# usb-serial.net
KiCad netlist of a schematic drawn in EAGLE
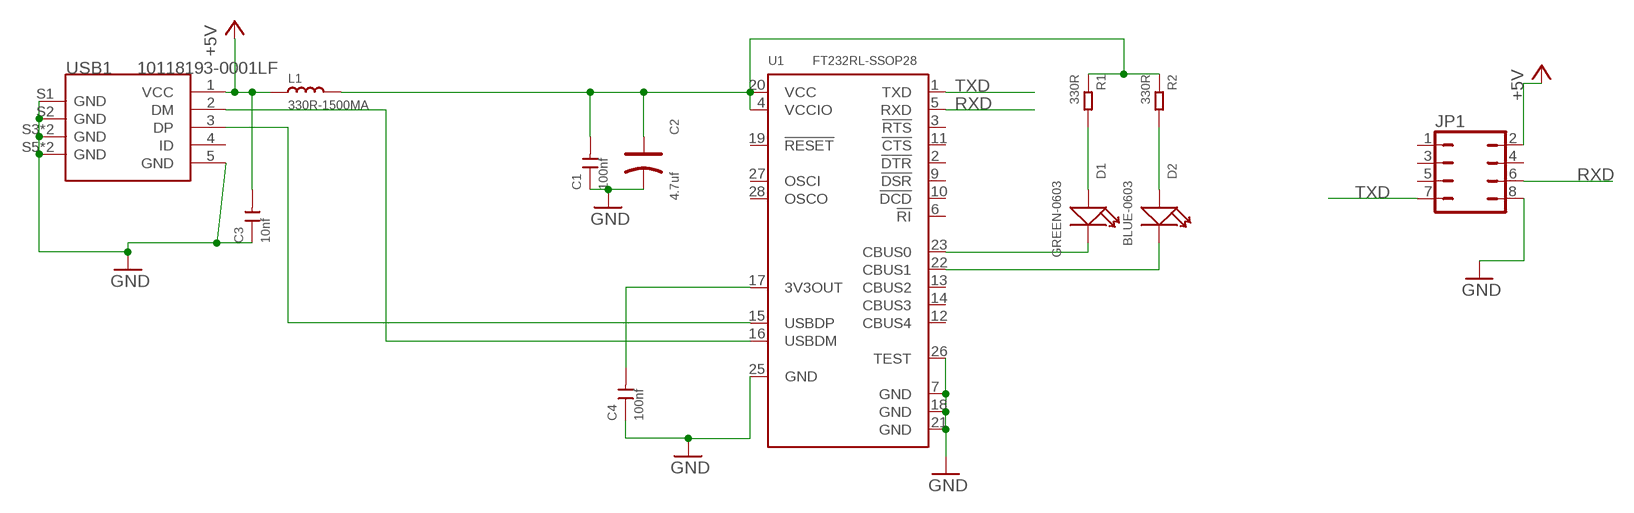
[diagram p0: schematic, sheet 1]

(export (version "E")
  (design (tool "Eeschema 10.0.6"))
  (components
    (comp (ref "C1")
      (value "100nf")
      (footprint "eagle-import:C0603")
      (fields (field (name "MPN") "CC0603KRX7R9BB104"))
      (libsource (lib "eagle-import") (part "CERAMIC-100NF-50V-10%-X7R(0603)"))
    )
    (comp (ref "C2")
      (value "4.7uf")
      (footprint "eagle-import:AVX-A")
      (fields (field (name "MPN") "TAJA475*016#NJ"))
      (libsource (lib "eagle-import") (part "TANTALUM-SMD-4.7UF-16V(AVX-A)"))
    )
    (comp (ref "C3")
      (value "10nf")
      (footprint "eagle-import:C0603")
      (fields (field (name "MPN") "CC0603KRX7R9BB103"))
      (libsource (lib "eagle-import") (part "CERAMIC-10NF-50V-10%-X7R(0603)"))
    )
    (comp (ref "C4")
      (value "100nf")
      (footprint "eagle-import:C0603")
      (fields (field (name "MPN") "CC0603KRX7R9BB104"))
      (libsource (lib "eagle-import") (part "CERAMIC-100NF-50V-10%-X7R(0603)"))
    )
    (comp (ref "D1")
      (value "GREEN-0603")
      (footprint "eagle-import:LED-0603")
      (fields (field (name "MPN") "19-217-G7C-AN1P2-3T"))
      (libsource (lib "eagle-import") (part "SMD-LED-CLEAR-GREEN(0603)"))
    )
    (comp (ref "D2")
      (value "BLUE-0603")
      (footprint "eagle-import:LED-0603")
      (fields (field (name "MPN") "19-217-BHC-ZL1M2RY-3T"))
      (libsource (lib "eagle-import") (part "SMD-LED-CLEAR-BLUE(0603)"))
    )
    (comp (ref "JP1")
      (value "JP4Q")
      (footprint "eagle-import:JP4Q")
      (libsource (lib "eagle-import") (part "JP4Q"))
    )
    (comp (ref "L1")
      (value "330R-1500MA")
      (footprint "eagle-import:L0805")
      (fields (field (name "MPN") "BLM21PG331SN1D"))
      (libsource (lib "eagle-import") (part "SMD-FERRITE-BEAD-330R-1500MA(0805)'0805'"))
    )
    (comp (ref "R1")
      (value "330R")
      (footprint "eagle-import:R0603")
      (fields (field (name "MPN") "RC0603FR-07330RL"))
      (libsource (lib "eagle-import") (part "SMD-RES-330R-1%-1/10W(0603)"))
    )
    (comp (ref "R2")
      (value "330R")
      (footprint "eagle-import:R0603")
      (fields (field (name "MPN") "RC0603FR-07330RL"))
      (libsource (lib "eagle-import") (part "SMD-RES-330R-1%-1/10W(0603)"))
    )
    (comp (ref "U1")
      (value "FT232RL-SSOP28")
      (footprint "eagle-import:SSOP28-0.65-10.2X5.2MM")
      (fields (field (name "MPN") "FT232RL"))
      (libsource (lib "eagle-import") (part "INTERFACE-FT232RL(SSOP28)"))
    )
    (comp (ref "USB1")
      (value "10118193-0001LF")
      (footprint "eagle-import:MICRO-USB5+6P-SMD-0.65-B")
      (libsource (lib "eagle-import") (part "MICRO-USB-SMD-B-(10118193-0001LF)"))
    )
  )
  (nets
    (net (code "1") (name "+5V") (class "Default")
      (node (ref "C3") (pin "2") (pinfunction "2_2") (pintype "passive"))
      (node (ref "JP1") (pin "2") (pinfunction "2_2") (pintype "passive"))
      (node (ref "L1") (pin "1") (pinfunction "1_1") (pintype "passive"))
      (node (ref "USB1") (pin "1") (pinfunction "VCC_1") (pintype "bidirectional"))
    )
    (net (code "2") (name "/RXD") (class "Default")
      (node (ref "JP1") (pin "6") (pinfunction "6_6") (pintype "passive"))
      (node (ref "U1") (pin "5") (pinfunction "RXD_5") (pintype "input"))
    )
    (net (code "3") (name "/TXD") (class "Default")
      (node (ref "JP1") (pin "7") (pinfunction "7_7") (pintype "passive"))
      (node (ref "U1") (pin "1") (pinfunction "TXD_1") (pintype "input"))
    )
    (net (code "4") (name "GND") (class "Default")
      (node (ref "C1") (pin "1") (pinfunction "1_1") (pintype "passive"))
      (node (ref "C2") (pin "-") (pinfunction "-_-") (pintype "passive"))
      (node (ref "C3") (pin "1") (pinfunction "1_1") (pintype "passive"))
      (node (ref "C4") (pin "1") (pinfunction "1_1") (pintype "passive"))
      (node (ref "JP1") (pin "8") (pinfunction "8_8") (pintype "passive"))
      (node (ref "U1") (pin "18") (pinfunction "GND_18") (pintype "input"))
      (node (ref "U1") (pin "21") (pinfunction "GND_21") (pintype "input"))
      (node (ref "U1") (pin "25") (pinfunction "GND_25") (pintype "input"))
      (node (ref "U1") (pin "26") (pinfunction "TEST_26") (pintype "input"))
      (node (ref "U1") (pin "7") (pinfunction "GND_7") (pintype "input"))
      (node (ref "USB1") (pin "5") (pinfunction "GND_5") (pintype "bidirectional"))
      (node (ref "USB1") (pin "S1") (pinfunction "GND_S1") (pintype "bidirectional"))
      (node (ref "USB1") (pin "S2") (pinfunction "GND_S2") (pintype "bidirectional"))
      (node (ref "USB1") (pin "S3") (pinfunction "GND_S3") (pintype "bidirectional"))
      (node (ref "USB1") (pin "S4") (pinfunction "GND_S4") (pintype "bidirectional"))
      (node (ref "USB1") (pin "S5") (pinfunction "GND_S5") (pintype "bidirectional"))
      (node (ref "USB1") (pin "S6") (pinfunction "GND_S6") (pintype "bidirectional"))
    )
    (net (code "5") (name "Net-(D1-Pad+)") (class "Default")
      (node (ref "D1") (pin "+") (pinfunction "+_+") (pintype "passive"))
      (node (ref "R1") (pin "2") (pinfunction "2_2") (pintype "passive"))
    )
    (net (code "6") (name "Net-(D2-Pad+)") (class "Default")
      (node (ref "D2") (pin "+") (pinfunction "+_+") (pintype "passive"))
      (node (ref "R2") (pin "2") (pinfunction "2_2") (pintype "passive"))
    )
    (net (code "7") (name "Net-(U1-3V3OUT)") (class "Default")
      (node (ref "C4") (pin "2") (pinfunction "2_2") (pintype "passive"))
      (node (ref "U1") (pin "17") (pinfunction "3V3OUT_17") (pintype "input"))
    )
    (net (code "8") (name "Net-(U1-CBUS0)") (class "Default")
      (node (ref "D1") (pin "-") (pinfunction "-_-") (pintype "passive"))
      (node (ref "U1") (pin "23") (pinfunction "CBUS0_23") (pintype "input"))
    )
    (net (code "9") (name "Net-(U1-CBUS1)") (class "Default")
      (node (ref "D2") (pin "-") (pinfunction "-_-") (pintype "passive"))
      (node (ref "U1") (pin "22") (pinfunction "CBUS1_22") (pintype "input"))
    )
    (net (code "10") (name "Net-(U1-USBDM)") (class "Default")
      (node (ref "U1") (pin "16") (pinfunction "USBDM_16") (pintype "input"))
      (node (ref "USB1") (pin "2") (pinfunction "DM_2") (pintype "bidirectional"))
    )
    (net (code "11") (name "Net-(U1-USBDP)") (class "Default")
      (node (ref "U1") (pin "15") (pinfunction "USBDP_15") (pintype "input"))
      (node (ref "USB1") (pin "3") (pinfunction "DP_3") (pintype "bidirectional"))
    )
    (net (code "12") (name "Net-(U1-VCC)") (class "Default")
      (node (ref "C1") (pin "2") (pinfunction "2_2") (pintype "passive"))
      (node (ref "C2") (pin "+") (pinfunction "+_+") (pintype "passive"))
      (node (ref "L1") (pin "2") (pinfunction "2_2") (pintype "passive"))
      (node (ref "R1") (pin "1") (pinfunction "1_1") (pintype "passive"))
      (node (ref "R2") (pin "1") (pinfunction "1_1") (pintype "passive"))
      (node (ref "U1") (pin "20") (pinfunction "VCC_20") (pintype "input"))
      (node (ref "U1") (pin "4") (pinfunction "VCCIO_4") (pintype "input"))
    )
    (net (code "13") (name "unconnected-(JP1-Pad1)") (class "Default")
      (node (ref "JP1") (pin "1") (pinfunction "1_1") (pintype "passive"))
    )
    (net (code "14") (name "unconnected-(JP1-Pad3)") (class "Default")
      (node (ref "JP1") (pin "3") (pinfunction "3_3") (pintype "passive"))
    )
    (net (code "15") (name "unconnected-(JP1-Pad4)") (class "Default")
      (node (ref "JP1") (pin "4") (pinfunction "4_4") (pintype "passive"))
    )
    (net (code "16") (name "unconnected-(JP1-Pad5)") (class "Default")
      (node (ref "JP1") (pin "5") (pinfunction "5_5") (pintype "passive"))
    )
    (net (code "17") (name "unconnected-(U1-CBUS2-Pad13)") (class "Default")
      (node (ref "U1") (pin "13") (pinfunction "CBUS2_13") (pintype "input"))
    )
    (net (code "18") (name "unconnected-(U1-CBUS3-Pad14)") (class "Default")
      (node (ref "U1") (pin "14") (pinfunction "CBUS3_14") (pintype "input"))
    )
    (net (code "19") (name "unconnected-(U1-CBUS4-Pad12)") (class "Default")
      (node (ref "U1") (pin "12") (pinfunction "CBUS4_12") (pintype "input"))
    )
    (net (code "20") (name "unconnected-(U1-OSCI-Pad27)") (class "Default")
      (node (ref "U1") (pin "27") (pinfunction "OSCI_27") (pintype "input"))
    )
    (net (code "21") (name "unconnected-(U1-OSCO-Pad28)") (class "Default")
      (node (ref "U1") (pin "28") (pinfunction "OSCO_28") (pintype "input"))
    )
    (net (code "22") (name "unconnected-(U1-~{CTS}-Pad11)") (class "Default")
      (node (ref "U1") (pin "11") (pinfunction "~{CTS}_11") (pintype "input"))
    )
    (net (code "23") (name "unconnected-(U1-~{DCD}-Pad10)") (class "Default")
      (node (ref "U1") (pin "10") (pinfunction "~{DCD}_10") (pintype "input"))
    )
    (net (code "24") (name "unconnected-(U1-~{DSR}-Pad9)") (class "Default")
      (node (ref "U1") (pin "9") (pinfunction "~{DSR}_9") (pintype "input"))
    )
    (net (code "25") (name "unconnected-(U1-~{DTR}-Pad2)") (class "Default")
      (node (ref "U1") (pin "2") (pinfunction "~{DTR}_2") (pintype "input"))
    )
    (net (code "26") (name "unconnected-(U1-~{RESET}-Pad19)") (class "Default")
      (node (ref "U1") (pin "19") (pinfunction "~{RESET}_19") (pintype "input"))
    )
    (net (code "27") (name "unconnected-(U1-~{RI}-Pad6)") (class "Default")
      (node (ref "U1") (pin "6") (pinfunction "~{RI}_6") (pintype "input"))
    )
    (net (code "28") (name "unconnected-(U1-~{RTS}-Pad3)") (class "Default")
      (node (ref "U1") (pin "3") (pinfunction "~{RTS}_3") (pintype "input"))
    )
    (net (code "29") (name "unconnected-(USB1-ID-Pad4)") (class "Default")
      (node (ref "USB1") (pin "4") (pinfunction "ID_4") (pintype "bidirectional"))
    )
  )
)
